# solar_collector_controller_V2.net
KiCad netlist of a schematic drawn in EAGLE
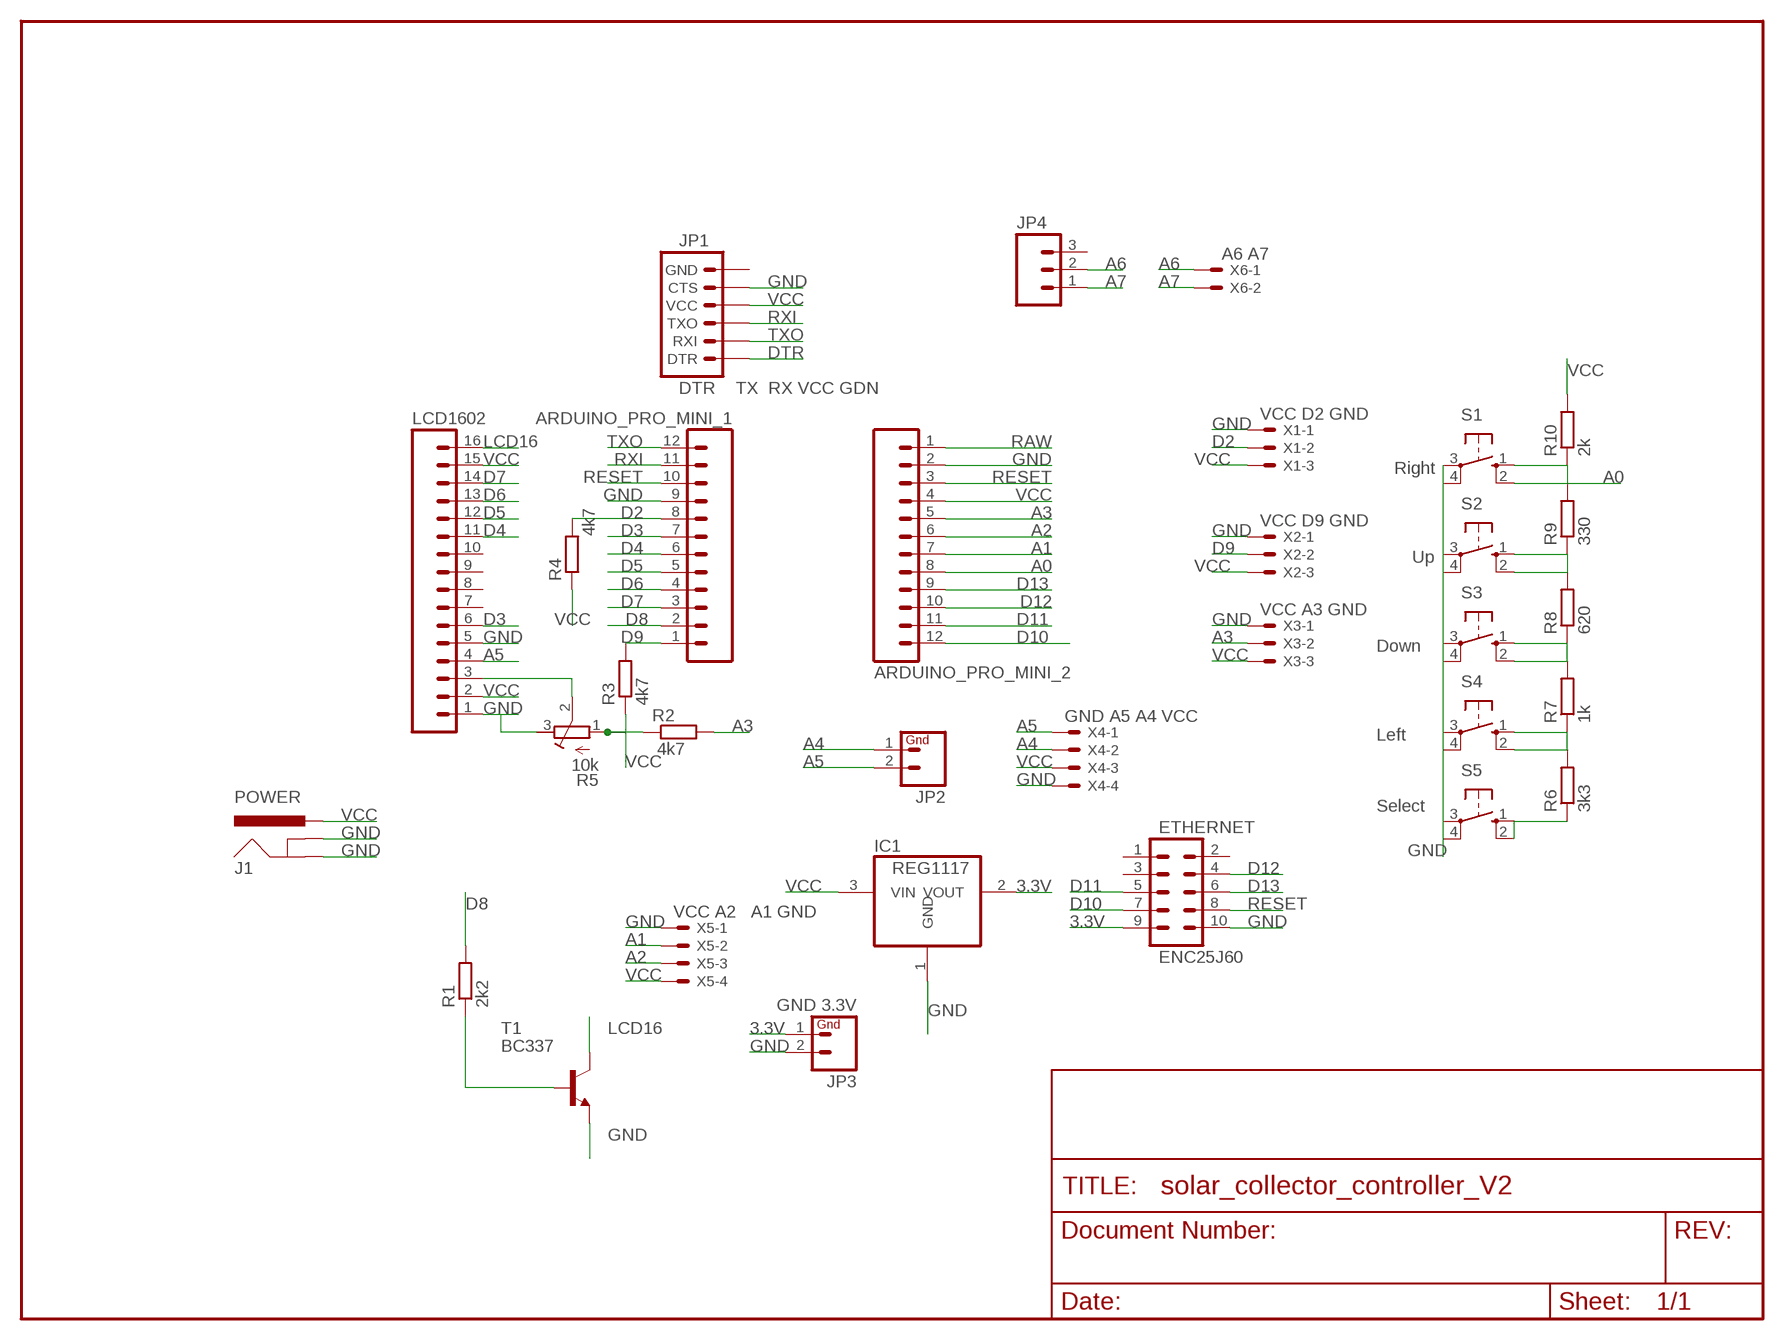
[diagram p0: schematic, sheet 1]

(export (version "E")
  (design (tool "Eeschema 10.0.6"))
  (components
    (comp (ref "ARDUINO_PRO_MINI_1")
      (value "M12PTH")
      (footprint "eagle-import:1X12")
      (libsource (lib "eagle-import") (part "M12PTH"))
    )
    (comp (ref "ARDUINO_PRO_MINI_2")
      (value "M12PTH")
      (footprint "eagle-import:1X12")
      (libsource (lib "eagle-import") (part "M12PTH"))
    )
    (comp (ref "ETHERNET")
      (value "ENC25J60")
      (footprint "eagle-import:AVR_ICSP")
      (libsource (lib "eagle-import") (part "M05X2PTH"))
    )
    (comp (ref "IC1")
      (value "REG1117")
      (footprint "eagle-import:SOT223")
      (libsource (lib "eagle-import") (part "REG1117"))
    )
    (comp (ref "J1")
      (value "POWER")
      (footprint "eagle-import:POWER_JACK_PTH_LOCK")
      (libsource (lib "eagle-import") (part "POWER_JACKPTH_LOCK"))
    )
    (comp (ref "JP1")
      (value "DTR TX RX VCC GDN")
      (footprint "eagle-import:1X06")
      (libsource (lib "eagle-import") (part "ARDUINO_SERIAL_PROGRAMPTH"))
    )
    (comp (ref "JP2")
      (value "M02PTH")
      (footprint "eagle-import:1X02")
      (libsource (lib "eagle-import") (part "M02PTH"))
    )
    (comp (ref "JP3")
      (value "GND 3.3V")
      (footprint "eagle-import:1X02")
      (libsource (lib "eagle-import") (part "M02PTH"))
    )
    (comp (ref "JP4")
      (value "M03PTH")
      (footprint "eagle-import:1X03")
      (libsource (lib "eagle-import") (part "M03PTH"))
    )
    (comp (ref "LCD1602")
      (value "HEADER-16P-2.54")
      (footprint "eagle-import:16P-2.54")
      (libsource (lib "eagle-import") (part "HEADER-16P-2.54"))
    )
    (comp (ref "R1")
      (value "2k2")
      (footprint "eagle-import:0207_10")
      (libsource (lib "eagle-import") (part "R-EU_0207/10"))
    )
    (comp (ref "R2")
      (value "4k7")
      (footprint "eagle-import:0207_10")
      (libsource (lib "eagle-import") (part "R-EU_0207/10"))
    )
    (comp (ref "R3")
      (value "4k7")
      (footprint "eagle-import:0207_10")
      (libsource (lib "eagle-import") (part "R-EU_0207/10"))
    )
    (comp (ref "R4")
      (value "4k7")
      (footprint "eagle-import:0207_10")
      (libsource (lib "eagle-import") (part "R-EU_0207/10"))
    )
    (comp (ref "R5")
      (value "10k")
      (footprint "eagle-import:RTRIM64W")
      (libsource (lib "eagle-import") (part "R-TRIMM64W"))
    )
    (comp (ref "R6")
      (value "3k3")
      (footprint "eagle-import:0207_10")
      (libsource (lib "eagle-import") (part "R-EU_0207/10"))
    )
    (comp (ref "R7")
      (value "1k")
      (footprint "eagle-import:0207_10")
      (libsource (lib "eagle-import") (part "R-EU_0207/10"))
    )
    (comp (ref "R8")
      (value "620")
      (footprint "eagle-import:0207_10")
      (libsource (lib "eagle-import") (part "R-EU_0207/10"))
    )
    (comp (ref "R9")
      (value "330")
      (footprint "eagle-import:0207_10")
      (libsource (lib "eagle-import") (part "R-EU_0207/10"))
    )
    (comp (ref "R10")
      (value "2k")
      (footprint "eagle-import:0207_10")
      (libsource (lib "eagle-import") (part "R-EU_0207/10"))
    )
    (comp (ref "S1")
      (value "Right")
      (footprint "eagle-import:B3F-10XX")
      (fields (field (name "MPN") "B3F-1000"))
      (libsource (lib "eagle-import") (part "10-XX"))
    )
    (comp (ref "S2")
      (value "Up")
      (footprint "eagle-import:B3F-10XX")
      (fields (field (name "MPN") "B3F-1000"))
      (libsource (lib "eagle-import") (part "10-XX"))
    )
    (comp (ref "S3")
      (value "Down")
      (footprint "eagle-import:B3F-10XX")
      (fields (field (name "MPN") "B3F-1000"))
      (libsource (lib "eagle-import") (part "10-XX"))
    )
    (comp (ref "S4")
      (value "Left")
      (footprint "eagle-import:B3F-10XX")
      (fields (field (name "MPN") "B3F-1000"))
      (libsource (lib "eagle-import") (part "10-XX"))
    )
    (comp (ref "S5")
      (value "Select")
      (footprint "eagle-import:B3F-10XX")
      (fields (field (name "MPN") "B3F-1000"))
      (libsource (lib "eagle-import") (part "10-XX"))
    )
    (comp (ref "T1")
      (value "BC337")
      (footprint "eagle-import:TO92")
      (libsource (lib "eagle-import") (part "BC337"))
    )
    (comp (ref "X1")
      (value "VCC D2 GND")
      (footprint "eagle-import:22-23-2031")
      (fields (field (name "MF") "MOLEX") (field (name "MPN") "22-23-2031"))
      (libsource (lib "eagle-import") (part "22-23-2031"))
    )
    (comp (ref "X2")
      (value "VCC D9 GND")
      (footprint "eagle-import:22-23-2031")
      (fields (field (name "MF") "MOLEX") (field (name "MPN") "22-23-2031"))
      (libsource (lib "eagle-import") (part "22-23-2031"))
    )
    (comp (ref "X3")
      (value "VCC A3 GND")
      (footprint "eagle-import:22-23-2031")
      (fields (field (name "MF") "MOLEX") (field (name "MPN") "22-23-2031"))
      (libsource (lib "eagle-import") (part "22-23-2031"))
    )
    (comp (ref "X4")
      (value "GND A5 A4 VCC")
      (footprint "eagle-import:22-23-2041")
      (fields (field (name "MF") "MOLEX") (field (name "MPN") "22-23-2041"))
      (libsource (lib "eagle-import") (part "22-23-2041"))
    )
    (comp (ref "X5")
      (value "VCC A2 A1 GND")
      (footprint "eagle-import:22-23-2041")
      (fields (field (name "MF") "MOLEX") (field (name "MPN") "22-23-2041"))
      (libsource (lib "eagle-import") (part "22-23-2041"))
    )
    (comp (ref "X6")
      (value "A6 A7")
      (footprint "eagle-import:22-23-2021")
      (fields (field (name "MF") "MOLEX") (field (name "MPN") "22-23-2021"))
      (libsource (lib "eagle-import") (part "22-23-2021"))
    )
  )
  (nets
    (net (code "1") (name "/3.3V") (class "Default")
      (node (ref "ETHERNET") (pin "9") (pinfunction "9_9") (pintype "passive"))
      (node (ref "IC1") (pin "2") (pinfunction "VOUT_2") (pintype "output"))
      (node (ref "JP3") (pin "1") (pinfunction "1_1") (pintype "passive"))
    )
    (net (code "2") (name "/A0") (class "Default")
      (node (ref "ARDUINO_PRO_MINI_2") (pin "8") (pinfunction "8_8") (pintype "passive"))
      (node (ref "R10") (pin "1") (pinfunction "1_1") (pintype "passive"))
      (node (ref "R9") (pin "2") (pinfunction "2_2") (pintype "passive"))
      (node (ref "S1") (pin "1") (pinfunction "S_1") (pintype "passive"))
      (node (ref "S1") (pin "2") (pinfunction "S1_2") (pintype "passive"))
    )
    (net (code "3") (name "/A1") (class "Default")
      (node (ref "ARDUINO_PRO_MINI_2") (pin "7") (pinfunction "7_7") (pintype "passive"))
      (node (ref "X5") (pin "2") (pinfunction "S_2") (pintype "passive"))
    )
    (net (code "4") (name "/A2") (class "Default")
      (node (ref "ARDUINO_PRO_MINI_2") (pin "6") (pinfunction "6_6") (pintype "passive"))
      (node (ref "X5") (pin "3") (pinfunction "S_3") (pintype "passive"))
    )
    (net (code "5") (name "/A3") (class "Default")
      (node (ref "ARDUINO_PRO_MINI_2") (pin "5") (pinfunction "5_5") (pintype "passive"))
      (node (ref "R2") (pin "2") (pinfunction "2_2") (pintype "passive"))
      (node (ref "X3") (pin "2") (pinfunction "S_2") (pintype "passive"))
    )
    (net (code "6") (name "/A4") (class "Default")
      (node (ref "JP2") (pin "1") (pinfunction "1_1") (pintype "passive"))
      (node (ref "X4") (pin "2") (pinfunction "S_2") (pintype "passive"))
    )
    (net (code "7") (name "/A5") (class "Default")
      (node (ref "JP2") (pin "2") (pinfunction "2_2") (pintype "passive"))
      (node (ref "LCD1602") (pin "4") (pinfunction "4_4") (pintype "passive"))
      (node (ref "X4") (pin "1") (pinfunction "S_1") (pintype "passive"))
    )
    (net (code "8") (name "/A6") (class "Default")
      (node (ref "JP4") (pin "2") (pinfunction "2_2") (pintype "passive"))
      (node (ref "X6") (pin "1") (pinfunction "S_1") (pintype "passive"))
    )
    (net (code "9") (name "/A7") (class "Default")
      (node (ref "JP4") (pin "1") (pinfunction "1_1") (pintype "passive"))
      (node (ref "X6") (pin "2") (pinfunction "S_2") (pintype "passive"))
    )
    (net (code "10") (name "/D2") (class "Default")
      (node (ref "ARDUINO_PRO_MINI_1") (pin "8") (pinfunction "8_8") (pintype "passive"))
      (node (ref "R4") (pin "2") (pinfunction "2_2") (pintype "passive"))
      (node (ref "X1") (pin "2") (pinfunction "S_2") (pintype "passive"))
    )
    (net (code "11") (name "/D3") (class "Default")
      (node (ref "ARDUINO_PRO_MINI_1") (pin "7") (pinfunction "7_7") (pintype "passive"))
      (node (ref "LCD1602") (pin "6") (pinfunction "6_6") (pintype "passive"))
    )
    (net (code "12") (name "/D4") (class "Default")
      (node (ref "ARDUINO_PRO_MINI_1") (pin "6") (pinfunction "6_6") (pintype "passive"))
      (node (ref "LCD1602") (pin "11") (pinfunction "11_11") (pintype "passive"))
    )
    (net (code "13") (name "/D5") (class "Default")
      (node (ref "ARDUINO_PRO_MINI_1") (pin "5") (pinfunction "5_5") (pintype "passive"))
      (node (ref "LCD1602") (pin "12") (pinfunction "12_12") (pintype "passive"))
    )
    (net (code "14") (name "/D6") (class "Default")
      (node (ref "ARDUINO_PRO_MINI_1") (pin "4") (pinfunction "4_4") (pintype "passive"))
      (node (ref "LCD1602") (pin "13") (pinfunction "13_13") (pintype "passive"))
    )
    (net (code "15") (name "/D7") (class "Default")
      (node (ref "ARDUINO_PRO_MINI_1") (pin "3") (pinfunction "3_3") (pintype "passive"))
      (node (ref "LCD1602") (pin "14") (pinfunction "14_14") (pintype "passive"))
    )
    (net (code "16") (name "/D8") (class "Default")
      (node (ref "ARDUINO_PRO_MINI_1") (pin "2") (pinfunction "2_2") (pintype "passive"))
      (node (ref "R1") (pin "2") (pinfunction "2_2") (pintype "passive"))
    )
    (net (code "17") (name "/D9") (class "Default")
      (node (ref "ARDUINO_PRO_MINI_1") (pin "1") (pinfunction "1_1") (pintype "passive"))
      (node (ref "R3") (pin "2") (pinfunction "2_2") (pintype "passive"))
      (node (ref "X2") (pin "2") (pinfunction "S_2") (pintype "passive"))
    )
    (net (code "18") (name "/D10") (class "Default")
      (node (ref "ARDUINO_PRO_MINI_2") (pin "12") (pinfunction "12_12") (pintype "passive"))
      (node (ref "ETHERNET") (pin "7") (pinfunction "7_7") (pintype "passive"))
    )
    (net (code "19") (name "/D11") (class "Default")
      (node (ref "ARDUINO_PRO_MINI_2") (pin "11") (pinfunction "11_11") (pintype "passive"))
      (node (ref "ETHERNET") (pin "5") (pinfunction "5_5") (pintype "passive"))
    )
    (net (code "20") (name "/D12") (class "Default")
      (node (ref "ARDUINO_PRO_MINI_2") (pin "10") (pinfunction "10_10") (pintype "passive"))
      (node (ref "ETHERNET") (pin "4") (pinfunction "4_4") (pintype "passive"))
    )
    (net (code "21") (name "/D13") (class "Default")
      (node (ref "ARDUINO_PRO_MINI_2") (pin "9") (pinfunction "9_9") (pintype "passive"))
      (node (ref "ETHERNET") (pin "6") (pinfunction "6_6") (pintype "passive"))
    )
    (net (code "22") (name "/DTR") (class "Default")
      (node (ref "JP1") (pin "1") (pinfunction "DTR_1") (pintype "passive"))
    )
    (net (code "23") (name "/GND") (class "Default")
      (node (ref "ARDUINO_PRO_MINI_1") (pin "9") (pinfunction "9_9") (pintype "passive"))
      (node (ref "ARDUINO_PRO_MINI_2") (pin "2") (pinfunction "2_2") (pintype "passive"))
      (node (ref "ETHERNET") (pin "10") (pinfunction "10_10") (pintype "passive"))
      (node (ref "IC1") (pin "1") (pinfunction "GND_1") (pintype "power_in"))
      (node (ref "J1") (pin "GND") (pinfunction "GND_GND") (pintype "bidirectional"))
      (node (ref "J1") (pin "GNDBREAK") (pinfunction "GNDBREAK_GNDBREAK") (pintype "bidirectional"))
      (node (ref "JP1") (pin "5") (pinfunction "CTS_5") (pintype "passive"))
      (node (ref "JP3") (pin "2") (pinfunction "2_2") (pintype "passive"))
      (node (ref "LCD1602") (pin "1") (pinfunction "1_1") (pintype "passive"))
      (node (ref "LCD1602") (pin "5") (pinfunction "5_5") (pintype "passive"))
      (node (ref "R5") (pin "3") (pinfunction "A_3") (pintype "passive"))
      (node (ref "S1") (pin "3") (pinfunction "P_3") (pintype "passive"))
      (node (ref "S1") (pin "4") (pinfunction "P1_4") (pintype "passive"))
      (node (ref "S2") (pin "3") (pinfunction "P_3") (pintype "passive"))
      (node (ref "S2") (pin "4") (pinfunction "P1_4") (pintype "passive"))
      (node (ref "S3") (pin "3") (pinfunction "P_3") (pintype "passive"))
      (node (ref "S3") (pin "4") (pinfunction "P1_4") (pintype "passive"))
      (node (ref "S4") (pin "3") (pinfunction "P_3") (pintype "passive"))
      (node (ref "S4") (pin "4") (pinfunction "P1_4") (pintype "passive"))
      (node (ref "S5") (pin "3") (pinfunction "P_3") (pintype "passive"))
      (node (ref "S5") (pin "4") (pinfunction "P1_4") (pintype "passive"))
      (node (ref "T1") (pin "1") (pinfunction "E_1") (pintype "passive"))
      (node (ref "X1") (pin "1") (pinfunction "S_1") (pintype "passive"))
      (node (ref "X2") (pin "1") (pinfunction "S_1") (pintype "passive"))
      (node (ref "X3") (pin "1") (pinfunction "S_1") (pintype "passive"))
      (node (ref "X4") (pin "4") (pinfunction "S_4") (pintype "passive"))
      (node (ref "X5") (pin "1") (pinfunction "S_1") (pintype "passive"))
    )
    (net (code "24") (name "/LCD16") (class "Default")
      (node (ref "LCD1602") (pin "16") (pinfunction "16_16") (pintype "passive"))
      (node (ref "T1") (pin "3") (pinfunction "C_3") (pintype "passive"))
    )
    (net (code "25") (name "/RAW") (class "Default")
      (node (ref "ARDUINO_PRO_MINI_2") (pin "1") (pinfunction "1_1") (pintype "passive"))
    )
    (net (code "26") (name "/RESET") (class "Default")
      (node (ref "ARDUINO_PRO_MINI_1") (pin "10") (pinfunction "10_10") (pintype "passive"))
      (node (ref "ARDUINO_PRO_MINI_2") (pin "3") (pinfunction "3_3") (pintype "passive"))
      (node (ref "ETHERNET") (pin "8") (pinfunction "8_8") (pintype "passive"))
    )
    (net (code "27") (name "/RXI") (class "Default")
      (node (ref "ARDUINO_PRO_MINI_1") (pin "11") (pinfunction "11_11") (pintype "passive"))
      (node (ref "JP1") (pin "3") (pinfunction "TXO_3") (pintype "passive"))
    )
    (net (code "28") (name "/TXO") (class "Default")
      (node (ref "ARDUINO_PRO_MINI_1") (pin "12") (pinfunction "12_12") (pintype "passive"))
      (node (ref "JP1") (pin "2") (pinfunction "RXI_2") (pintype "passive"))
    )
    (net (code "29") (name "/VCC") (class "Default")
      (node (ref "ARDUINO_PRO_MINI_2") (pin "4") (pinfunction "4_4") (pintype "passive"))
      (node (ref "IC1") (pin "3") (pinfunction "VIN_3") (pintype "input"))
      (node (ref "J1") (pin "PWR") (pinfunction "PWR_PWR") (pintype "bidirectional"))
      (node (ref "JP1") (pin "4") (pinfunction "VCC_4") (pintype "passive"))
      (node (ref "LCD1602") (pin "15") (pinfunction "15_15") (pintype "passive"))
      (node (ref "LCD1602") (pin "2") (pinfunction "2_2") (pintype "passive"))
      (node (ref "R10") (pin "2") (pinfunction "2_2") (pintype "passive"))
      (node (ref "R2") (pin "1") (pinfunction "1_1") (pintype "passive"))
      (node (ref "R3") (pin "1") (pinfunction "1_1") (pintype "passive"))
      (node (ref "R4") (pin "1") (pinfunction "1_1") (pintype "passive"))
      (node (ref "R5") (pin "1") (pinfunction "E_1") (pintype "passive"))
      (node (ref "X1") (pin "3") (pinfunction "S_3") (pintype "passive"))
      (node (ref "X2") (pin "3") (pinfunction "S_3") (pintype "passive"))
      (node (ref "X3") (pin "3") (pinfunction "S_3") (pintype "passive"))
      (node (ref "X4") (pin "3") (pinfunction "S_3") (pintype "passive"))
      (node (ref "X5") (pin "4") (pinfunction "S_4") (pintype "passive"))
    )
    (net (code "30") (name "Net-(R5-S)") (class "Default")
      (node (ref "LCD1602") (pin "3") (pinfunction "3_3") (pintype "passive"))
      (node (ref "R5") (pin "2") (pinfunction "S_2") (pintype "passive"))
    )
    (net (code "31") (name "Net-(S2-S)") (class "Default")
      (node (ref "R8") (pin "2") (pinfunction "2_2") (pintype "passive"))
      (node (ref "R9") (pin "1") (pinfunction "1_1") (pintype "passive"))
      (node (ref "S2") (pin "1") (pinfunction "S_1") (pintype "passive"))
      (node (ref "S2") (pin "2") (pinfunction "S1_2") (pintype "passive"))
    )
    (net (code "32") (name "Net-(S3-S)") (class "Default")
      (node (ref "R7") (pin "2") (pinfunction "2_2") (pintype "passive"))
      (node (ref "R8") (pin "1") (pinfunction "1_1") (pintype "passive"))
      (node (ref "S3") (pin "1") (pinfunction "S_1") (pintype "passive"))
      (node (ref "S3") (pin "2") (pinfunction "S1_2") (pintype "passive"))
    )
    (net (code "33") (name "Net-(S4-S)") (class "Default")
      (node (ref "R6") (pin "2") (pinfunction "2_2") (pintype "passive"))
      (node (ref "R7") (pin "1") (pinfunction "1_1") (pintype "passive"))
      (node (ref "S4") (pin "1") (pinfunction "S_1") (pintype "passive"))
      (node (ref "S4") (pin "2") (pinfunction "S1_2") (pintype "passive"))
    )
    (net (code "34") (name "Net-(S5-S)") (class "Default")
      (node (ref "R6") (pin "1") (pinfunction "1_1") (pintype "passive"))
      (node (ref "S5") (pin "1") (pinfunction "S_1") (pintype "passive"))
      (node (ref "S5") (pin "2") (pinfunction "S1_2") (pintype "passive"))
    )
    (net (code "35") (name "Net-(T1-B)") (class "Default")
      (node (ref "R1") (pin "1") (pinfunction "1_1") (pintype "passive"))
      (node (ref "T1") (pin "2") (pinfunction "B_2") (pintype "passive"))
    )
    (net (code "36") (name "unconnected-(ETHERNET-Pad1)") (class "Default")
      (node (ref "ETHERNET") (pin "1") (pinfunction "1_1") (pintype "passive"))
    )
    (net (code "37") (name "unconnected-(ETHERNET-Pad2)") (class "Default")
      (node (ref "ETHERNET") (pin "2") (pinfunction "2_2") (pintype "passive"))
    )
    (net (code "38") (name "unconnected-(ETHERNET-Pad3)") (class "Default")
      (node (ref "ETHERNET") (pin "3") (pinfunction "3_3") (pintype "passive"))
    )
    (net (code "39") (name "unconnected-(JP1-GND-Pad6)") (class "Default")
      (node (ref "JP1") (pin "6") (pinfunction "GND_6") (pintype "passive"))
    )
    (net (code "40") (name "unconnected-(JP4-Pad3)") (class "Default")
      (node (ref "JP4") (pin "3") (pinfunction "3_3") (pintype "passive"))
    )
    (net (code "41") (name "unconnected-(LCD1602-Pad7)") (class "Default")
      (node (ref "LCD1602") (pin "7") (pinfunction "7_7") (pintype "passive"))
    )
    (net (code "42") (name "unconnected-(LCD1602-Pad8)") (class "Default")
      (node (ref "LCD1602") (pin "8") (pinfunction "8_8") (pintype "passive"))
    )
    (net (code "43") (name "unconnected-(LCD1602-Pad9)") (class "Default")
      (node (ref "LCD1602") (pin "9") (pinfunction "9_9") (pintype "passive"))
    )
    (net (code "44") (name "unconnected-(LCD1602-Pad10)") (class "Default")
      (node (ref "LCD1602") (pin "10") (pinfunction "10_10") (pintype "passive"))
    )
  )
)
